# validation-board-final.net
KiCad netlist of a schematic drawn in EAGLE
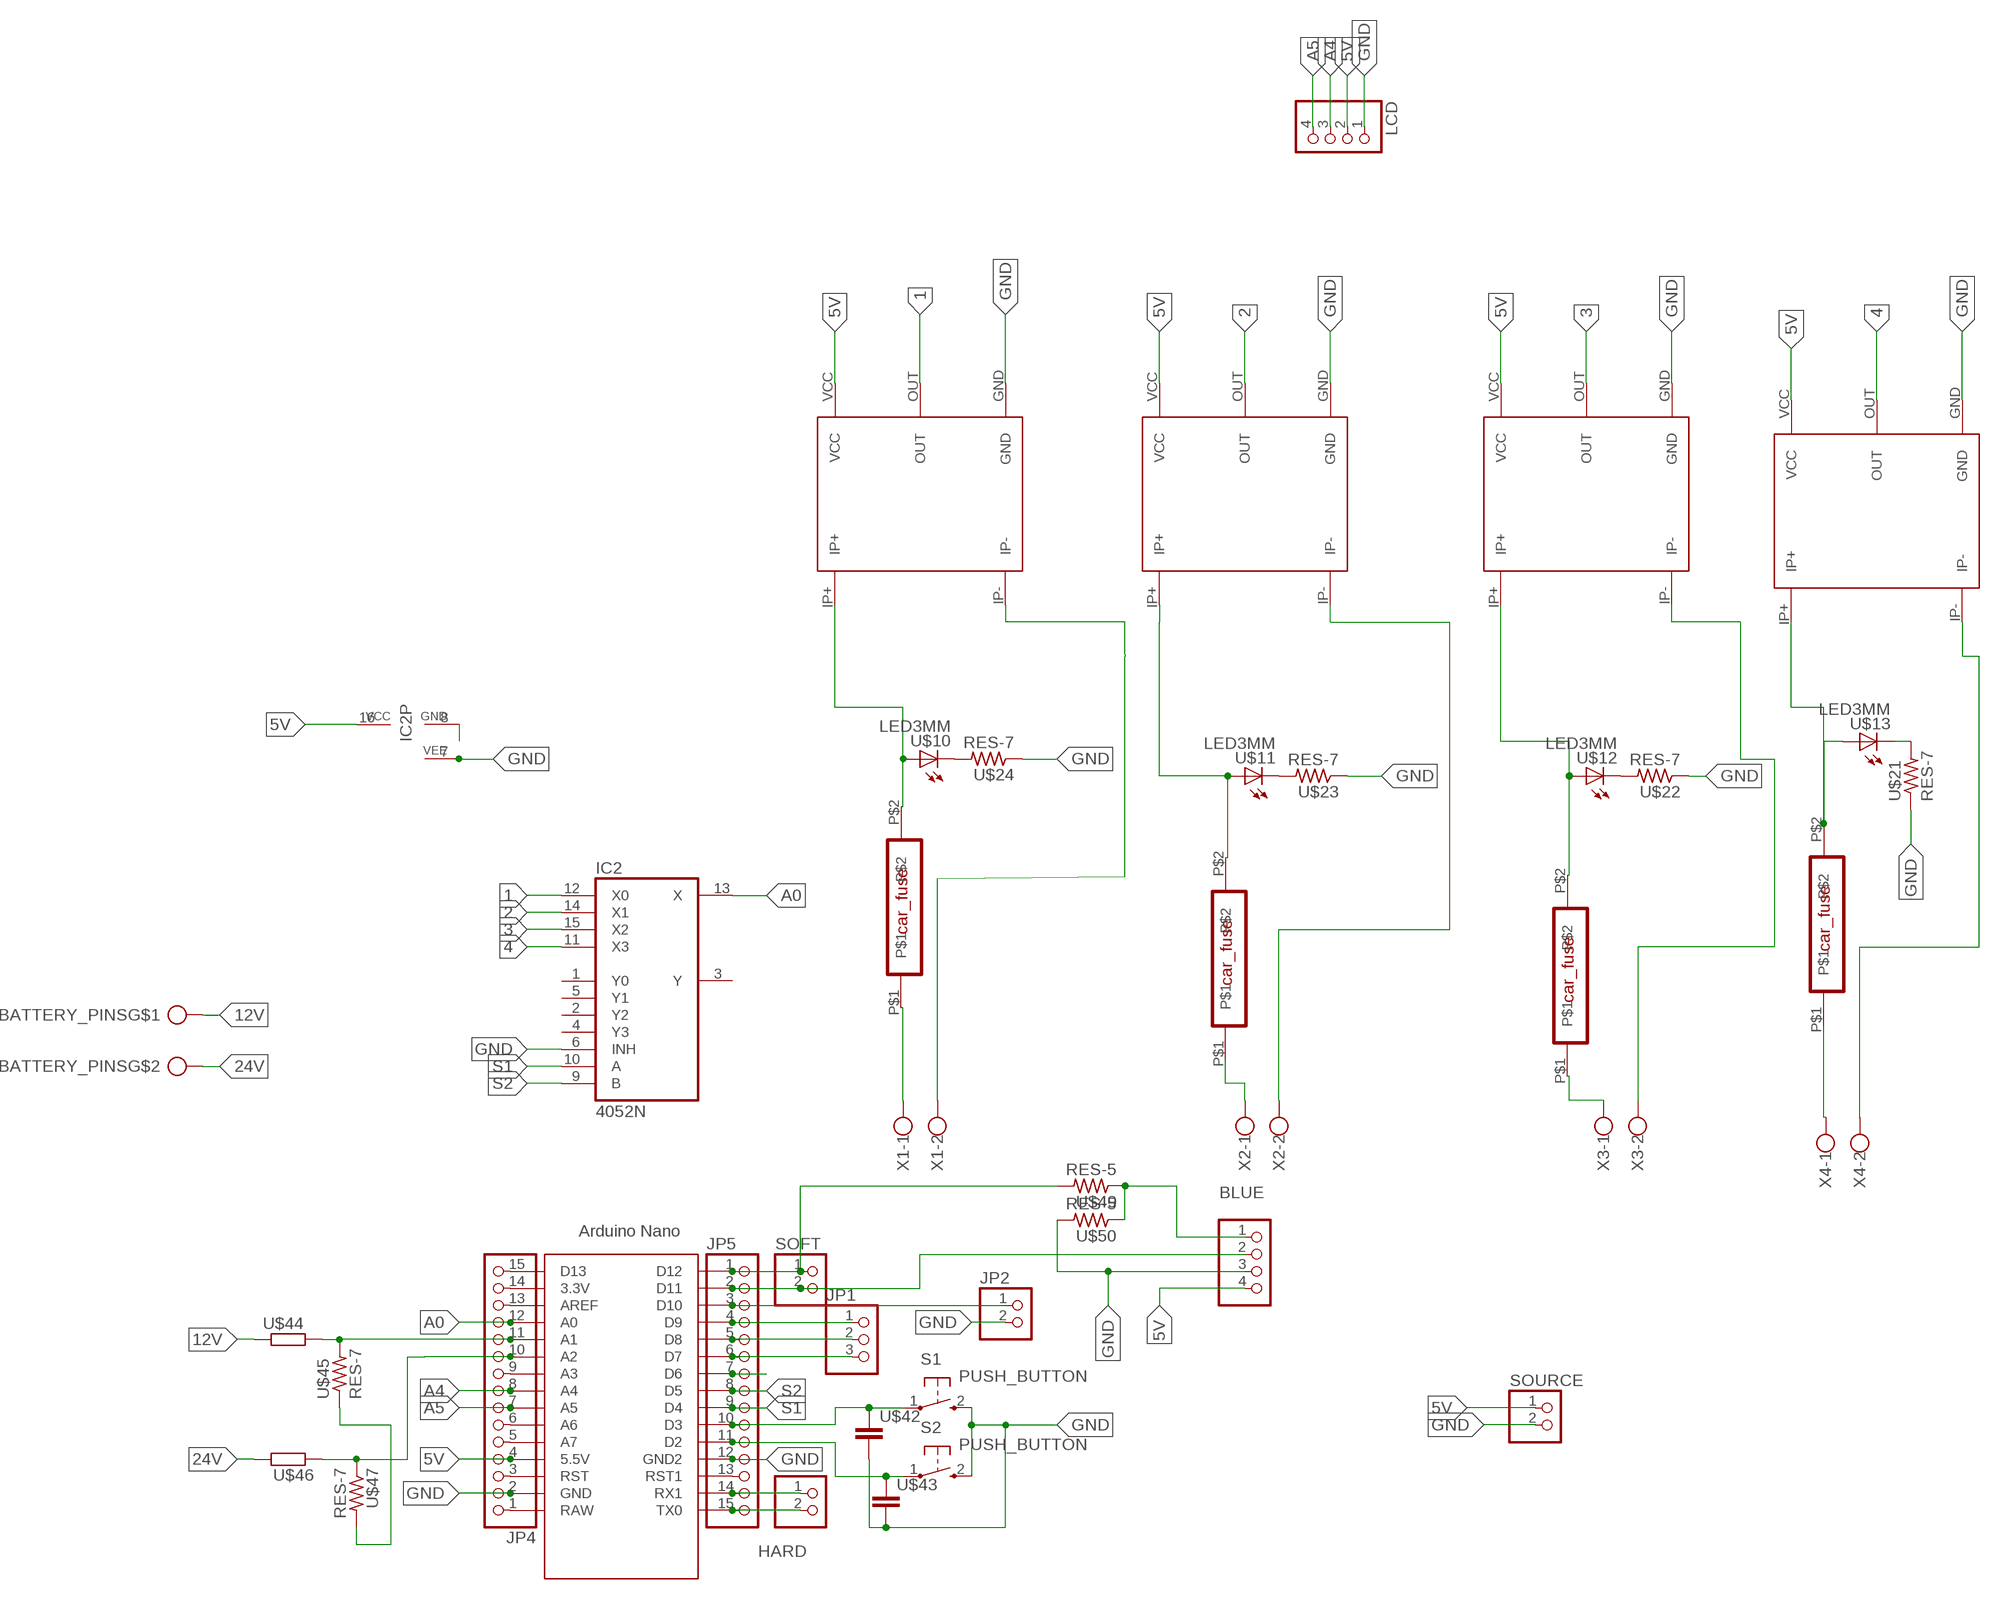
[diagram p0: schematic, sheet 1]

(export (version "E")
  (design (tool "Eeschema 10.0.6"))
  (components
    (comp (ref "BATTERY_PINS")
      (value "CON_PTR_2")
      (footprint "eagle-import:AK300_2")
      (libsource (lib "eagle-import") (part "CON_PTR_2"))
    )
    (comp (ref "BLUE")
      (value "PINHD-4_DATA")
      (footprint "eagle-import:1X04_DATA")
      (libsource (lib "eagle-import") (part "PINHD-4_DATA"))
    )
    (comp (ref "HARD")
      (value "PINHD-2_DATA")
      (footprint "eagle-import:1X02_DATA")
      (libsource (lib "eagle-import") (part "PINHD-2_DATA"))
    )
    (comp (ref "IC2")
      (value "4052N")
      (footprint "eagle-import:DIL16")
      (libsource (lib "eagle-import") (part "4052N"))
    )
    (comp (ref "JP1")
      (value "PINHD-3_DATA")
      (footprint "eagle-import:1X03_DATA")
      (libsource (lib "eagle-import") (part "PINHD-3_DATA"))
    )
    (comp (ref "JP2")
      (value "PINHD-2_DATA")
      (footprint "eagle-import:1X02_DATA")
      (libsource (lib "eagle-import") (part "PINHD-2_DATA"))
    )
    (comp (ref "JP4")
      (value "PINHD-1X15")
      (footprint "eagle-import:1X15")
      (libsource (lib "eagle-import") (part "PINHD-1X15"))
    )
    (comp (ref "JP5")
      (value "PINHD-1X15")
      (footprint "eagle-import:1X15")
      (libsource (lib "eagle-import") (part "PINHD-1X15"))
    )
    (comp (ref "LCD")
      (value "PINHD-4_DATA")
      (footprint "eagle-import:1X04_DATA")
      (libsource (lib "eagle-import") (part "PINHD-4_DATA"))
    )
    (comp (ref "S1")
      (value "PUSH_BUTTON")
      (footprint "eagle-import:B3F-10XX")
      (libsource (lib "eagle-import") (part "PUSH_BUTTON"))
    )
    (comp (ref "S2")
      (value "PUSH_BUTTON")
      (footprint "eagle-import:B3F-10XX")
      (libsource (lib "eagle-import") (part "PUSH_BUTTON"))
    )
    (comp (ref "SOFT")
      (value "PINHD-2_DATA")
      (footprint "eagle-import:1X02_DATA")
      (libsource (lib "eagle-import") (part "PINHD-2_DATA"))
    )
    (comp (ref "SOURCE")
      (value "PINHD-2_DATA")
      (footprint "eagle-import:1X02_DATA")
      (libsource (lib "eagle-import") (part "PINHD-2_DATA"))
    )
    (comp (ref "U$1")
      (value "ARDUINO_NANO")
      (footprint "eagle-import:NANO")
      (libsource (lib "eagle-import") (part "ARDUINO_NANO"))
    )
    (comp (ref "U$2")
      (value "CAR_FUSE")
      (footprint "eagle-import:CAR_FUSE")
      (libsource (lib "eagle-import") (part "CAR_FUSE"))
    )
    (comp (ref "U$3")
      (value "CAR_FUSE")
      (footprint "eagle-import:CAR_FUSE")
      (libsource (lib "eagle-import") (part "CAR_FUSE"))
    )
    (comp (ref "U$4")
      (value "CAR_FUSE")
      (footprint "eagle-import:CAR_FUSE")
      (libsource (lib "eagle-import") (part "CAR_FUSE"))
    )
    (comp (ref "U$5")
      (value "CAR_FUSE")
      (footprint "eagle-import:CAR_FUSE")
      (libsource (lib "eagle-import") (part "CAR_FUSE"))
    )
    (comp (ref "U$10")
      (value "LED3MM")
      (footprint "eagle-import:LED3MM")
      (libsource (lib "eagle-import") (part "LED3MM"))
    )
    (comp (ref "U$11")
      (value "LED3MM")
      (footprint "eagle-import:LED3MM")
      (libsource (lib "eagle-import") (part "LED3MM"))
    )
    (comp (ref "U$12")
      (value "LED3MM")
      (footprint "eagle-import:LED3MM")
      (libsource (lib "eagle-import") (part "LED3MM"))
    )
    (comp (ref "U$13")
      (value "LED3MM")
      (footprint "eagle-import:LED3MM")
      (libsource (lib "eagle-import") (part "LED3MM"))
    )
    (comp (ref "U$21")
      (value "RES-7")
      (footprint "eagle-import:0204_7")
      (libsource (lib "eagle-import") (part "RES-7"))
    )
    (comp (ref "U$22")
      (value "RES-7")
      (footprint "eagle-import:0204_7")
      (libsource (lib "eagle-import") (part "RES-7"))
    )
    (comp (ref "U$23")
      (value "RES-7")
      (footprint "eagle-import:0204_7")
      (libsource (lib "eagle-import") (part "RES-7"))
    )
    (comp (ref "U$24")
      (value "RES-7")
      (footprint "eagle-import:0204_7")
      (libsource (lib "eagle-import") (part "RES-7"))
    )
    (comp (ref "U$26")
      (value "ASC712_MODULE")
      (footprint "eagle-import:ASC712_MODULE")
      (libsource (lib "eagle-import") (part "ASC712_MODULE"))
    )
    (comp (ref "U$27")
      (value "ASC712_MODULE")
      (footprint "eagle-import:ASC712_MODULE")
      (libsource (lib "eagle-import") (part "ASC712_MODULE"))
    )
    (comp (ref "U$28")
      (value "ASC712_MODULE")
      (footprint "eagle-import:ASC712_MODULE")
      (libsource (lib "eagle-import") (part "ASC712_MODULE"))
    )
    (comp (ref "U$29")
      (value "ASC712_MODULE")
      (footprint "eagle-import:ASC712_MODULE")
      (libsource (lib "eagle-import") (part "ASC712_MODULE"))
    )
    (comp (ref "U$42")
      (value "CAPACITOR")
      (footprint "eagle-import:C025-025X050")
      (libsource (lib "eagle-import") (part "CAPACITOR"))
    )
    (comp (ref "U$43")
      (value "CAPACITOR")
      (footprint "eagle-import:C025-025X050")
      (libsource (lib "eagle-import") (part "CAPACITOR"))
    )
    (comp (ref "U$44")
      (value "R-EU_0207/10")
      (footprint "eagle-import:0207_10")
      (libsource (lib "eagle-import") (part "R-EU_0207/10"))
    )
    (comp (ref "U$45")
      (value "RES-7")
      (footprint "eagle-import:0204_7")
      (libsource (lib "eagle-import") (part "RES-7"))
    )
    (comp (ref "U$46")
      (value "R-EU_0207/10")
      (footprint "eagle-import:0207_10")
      (libsource (lib "eagle-import") (part "R-EU_0207/10"))
    )
    (comp (ref "U$47")
      (value "RES-7")
      (footprint "eagle-import:0204_7")
      (libsource (lib "eagle-import") (part "RES-7"))
    )
    (comp (ref "U$49")
      (value "RES-5")
      (footprint "eagle-import:0204_5")
      (libsource (lib "eagle-import") (part "RES-5"))
    )
    (comp (ref "U$50")
      (value "RES-5")
      (footprint "eagle-import:0204_5")
      (libsource (lib "eagle-import") (part "RES-5"))
    )
    (comp (ref "X1")
      (value "ROSTA.POWER")
      (footprint "eagle-import:W239-302")
      (libsource (lib "eagle-import") (part "ROSTA.POWER"))
    )
    (comp (ref "X2")
      (value "ROSTA.POWER")
      (footprint "eagle-import:W239-302")
      (libsource (lib "eagle-import") (part "ROSTA.POWER"))
    )
    (comp (ref "X3")
      (value "ROSTA.POWER")
      (footprint "eagle-import:W239-302")
      (libsource (lib "eagle-import") (part "ROSTA.POWER"))
    )
    (comp (ref "X4")
      (value "ROSTA.POWER")
      (footprint "eagle-import:W239-302")
      (libsource (lib "eagle-import") (part "ROSTA.POWER"))
    )
  )
  (nets
    (net (code "1") (name "1") (class "Default")
      (node (ref "IC2") (pin "12") (pinfunction "X0_12") (pintype "bidirectional"))
      (node (ref "U$26") (pin "OUT") (pinfunction "OUT_OUT") (pintype "bidirectional"))
    )
    (net (code "2") (name "2") (class "Default")
      (node (ref "IC2") (pin "14") (pinfunction "X1_14") (pintype "bidirectional"))
      (node (ref "U$27") (pin "OUT") (pinfunction "OUT_OUT") (pintype "bidirectional"))
    )
    (net (code "3") (name "3") (class "Default")
      (node (ref "IC2") (pin "15") (pinfunction "X2_15") (pintype "bidirectional"))
      (node (ref "U$28") (pin "OUT") (pinfunction "OUT_OUT") (pintype "bidirectional"))
    )
    (net (code "4") (name "4") (class "Default")
      (node (ref "IC2") (pin "11") (pinfunction "X3_11") (pintype "bidirectional"))
      (node (ref "U$29") (pin "OUT") (pinfunction "OUT_OUT") (pintype "bidirectional"))
    )
    (net (code "5") (name "5V") (class "Default")
      (node (ref "BLUE") (pin "4") (pinfunction "4_4") (pintype "passive"))
      (node (ref "IC2") (pin "16") (pinfunction "VCC_16") (pintype "power_in"))
      (node (ref "JP4") (pin "4") (pinfunction "4_4") (pintype "passive"))
      (node (ref "LCD") (pin "2") (pinfunction "2_2") (pintype "passive"))
      (node (ref "SOURCE") (pin "1") (pinfunction "1_1") (pintype "passive"))
      (node (ref "U$1") (pin "5V") (pinfunction "5.5V_5V") (pintype "bidirectional"))
      (node (ref "U$26") (pin "VCC") (pinfunction "VCC_VCC") (pintype "bidirectional"))
      (node (ref "U$27") (pin "VCC") (pinfunction "VCC_VCC") (pintype "bidirectional"))
      (node (ref "U$28") (pin "VCC") (pinfunction "VCC_VCC") (pintype "bidirectional"))
      (node (ref "U$29") (pin "VCC") (pinfunction "VCC_VCC") (pintype "bidirectional"))
    )
    (net (code "6") (name "12V") (class "Default")
      (node (ref "BATTERY_PINS") (pin "1") (pinfunction "KL_1") (pintype "passive"))
      (node (ref "U$44") (pin "1") (pinfunction "1_1") (pintype "passive"))
    )
    (net (code "7") (name "24V") (class "Default")
      (node (ref "BATTERY_PINS") (pin "2") (pinfunction "KL_2") (pintype "passive"))
      (node (ref "U$46") (pin "2") (pinfunction "2_2") (pintype "passive"))
    )
    (net (code "8") (name "A0") (class "Default")
      (node (ref "IC2") (pin "13") (pinfunction "X_13") (pintype "bidirectional"))
      (node (ref "JP4") (pin "12") (pinfunction "12_12") (pintype "passive"))
      (node (ref "U$1") (pin "A0") (pinfunction "A0_A0") (pintype "bidirectional"))
    )
    (net (code "9") (name "A4") (class "Default")
      (node (ref "JP4") (pin "8") (pinfunction "8_8") (pintype "passive"))
      (node (ref "LCD") (pin "3") (pinfunction "3_3") (pintype "passive"))
      (node (ref "U$1") (pin "A4") (pinfunction "A4_A4") (pintype "bidirectional"))
    )
    (net (code "10") (name "A5") (class "Default")
      (node (ref "JP4") (pin "7") (pinfunction "7_7") (pintype "passive"))
      (node (ref "LCD") (pin "4") (pinfunction "4_4") (pintype "passive"))
      (node (ref "U$1") (pin "A5") (pinfunction "A5_A5") (pintype "bidirectional"))
    )
    (net (code "11") (name "GND") (class "Default")
      (node (ref "BLUE") (pin "3") (pinfunction "3_3") (pintype "passive"))
      (node (ref "IC2") (pin "6") (pinfunction "INH_6") (pintype "input"))
      (node (ref "IC2") (pin "7") (pinfunction "VEE_7") (pintype "power_in"))
      (node (ref "JP2") (pin "2") (pinfunction "2_2") (pintype "passive"))
      (node (ref "JP4") (pin "2") (pinfunction "2_2") (pintype "passive"))
      (node (ref "JP5") (pin "12") (pinfunction "12_12") (pintype "passive"))
      (node (ref "LCD") (pin "1") (pinfunction "1_1") (pintype "passive"))
      (node (ref "S1") (pin "2") (pinfunction "S_2") (pintype "passive"))
      (node (ref "S2") (pin "2") (pinfunction "S_2") (pintype "passive"))
      (node (ref "SOURCE") (pin "2") (pinfunction "2_2") (pintype "passive"))
      (node (ref "U$1") (pin "GND") (pinfunction "GND_GND") (pintype "bidirectional"))
      (node (ref "U$1") (pin "GND1") (pinfunction "GND2_GND1") (pintype "bidirectional"))
      (node (ref "U$21") (pin "1") (pinfunction "1_1") (pintype "passive"))
      (node (ref "U$22") (pin "1") (pinfunction "1_1") (pintype "passive"))
      (node (ref "U$23") (pin "1") (pinfunction "1_1") (pintype "passive"))
      (node (ref "U$24") (pin "1") (pinfunction "1_1") (pintype "passive"))
      (node (ref "U$26") (pin "GND") (pinfunction "GND_GND") (pintype "bidirectional"))
      (node (ref "U$27") (pin "GND") (pinfunction "GND_GND") (pintype "bidirectional"))
      (node (ref "U$28") (pin "GND") (pinfunction "GND_GND") (pintype "bidirectional"))
      (node (ref "U$29") (pin "GND") (pinfunction "GND_GND") (pintype "bidirectional"))
      (node (ref "U$42") (pin "2") (pinfunction "2_2") (pintype "passive"))
      (node (ref "U$43") (pin "2") (pinfunction "2_2") (pintype "passive"))
      (node (ref "U$50") (pin "2") (pinfunction "2_2") (pintype "passive"))
    )
    (net (code "12") (name "Net-(BLUE-Pad1)") (class "Default")
      (node (ref "BLUE") (pin "1") (pinfunction "1_1") (pintype "passive"))
      (node (ref "U$49") (pin "1") (pinfunction "1_1") (pintype "passive"))
      (node (ref "U$50") (pin "1") (pinfunction "1_1") (pintype "passive"))
    )
    (net (code "13") (name "Net-(BLUE-Pad2)") (class "Default")
      (node (ref "BLUE") (pin "2") (pinfunction "2_2") (pintype "passive"))
      (node (ref "JP5") (pin "2") (pinfunction "2_2") (pintype "passive"))
      (node (ref "SOFT") (pin "2") (pinfunction "2_2") (pintype "passive"))
      (node (ref "U$1") (pin "D11") (pinfunction "D11_D11") (pintype "bidirectional"))
    )
    (net (code "14") (name "Net-(HARD-Pad1)") (class "Default")
      (node (ref "HARD") (pin "1") (pinfunction "1_1") (pintype "passive"))
      (node (ref "JP5") (pin "14") (pinfunction "14_14") (pintype "passive"))
      (node (ref "U$1") (pin "RX1") (pinfunction "RX1_RX1") (pintype "bidirectional"))
    )
    (net (code "15") (name "Net-(HARD-Pad2)") (class "Default")
      (node (ref "HARD") (pin "2") (pinfunction "2_2") (pintype "passive"))
      (node (ref "JP5") (pin "15") (pinfunction "15_15") (pintype "passive"))
      (node (ref "U$1") (pin "TX0") (pinfunction "TX0_TX0") (pintype "bidirectional"))
    )
    (net (code "16") (name "Net-(JP1-Pad1)") (class "Default")
      (node (ref "JP1") (pin "1") (pinfunction "1_1") (pintype "passive"))
      (node (ref "JP5") (pin "4") (pinfunction "4_4") (pintype "passive"))
      (node (ref "U$1") (pin "D9") (pinfunction "D9_D9") (pintype "bidirectional"))
    )
    (net (code "17") (name "Net-(JP1-Pad2)") (class "Default")
      (node (ref "JP1") (pin "2") (pinfunction "2_2") (pintype "passive"))
      (node (ref "JP5") (pin "5") (pinfunction "5_5") (pintype "passive"))
      (node (ref "U$1") (pin "D8") (pinfunction "D8_D8") (pintype "bidirectional"))
    )
    (net (code "18") (name "Net-(JP1-Pad3)") (class "Default")
      (node (ref "JP1") (pin "3") (pinfunction "3_3") (pintype "passive"))
      (node (ref "JP5") (pin "6") (pinfunction "6_6") (pintype "passive"))
      (node (ref "U$1") (pin "D7") (pinfunction "D7_D7") (pintype "bidirectional"))
    )
    (net (code "19") (name "Net-(JP2-Pad1)") (class "Default")
      (node (ref "JP2") (pin "1") (pinfunction "1_1") (pintype "passive"))
      (node (ref "JP5") (pin "3") (pinfunction "3_3") (pintype "passive"))
      (node (ref "U$1") (pin "D10") (pinfunction "D10_D10") (pintype "bidirectional"))
    )
    (net (code "20") (name "Net-(JP4-Pad1)") (class "Default")
      (node (ref "JP4") (pin "1") (pinfunction "1_1") (pintype "passive"))
      (node (ref "U$1") (pin "RAW") (pinfunction "RAW_RAW") (pintype "bidirectional"))
    )
    (net (code "21") (name "Net-(JP4-Pad3)") (class "Default")
      (node (ref "JP4") (pin "3") (pinfunction "3_3") (pintype "passive"))
      (node (ref "U$1") (pin "RST") (pinfunction "RST_RST") (pintype "bidirectional"))
    )
    (net (code "22") (name "Net-(JP4-Pad5)") (class "Default")
      (node (ref "JP4") (pin "5") (pinfunction "5_5") (pintype "passive"))
      (node (ref "U$1") (pin "A7") (pinfunction "A7_A7") (pintype "bidirectional"))
    )
    (net (code "23") (name "Net-(JP4-Pad6)") (class "Default")
      (node (ref "JP4") (pin "6") (pinfunction "6_6") (pintype "passive"))
      (node (ref "U$1") (pin "A6") (pinfunction "A6_A6") (pintype "bidirectional"))
    )
    (net (code "24") (name "Net-(JP4-Pad9)") (class "Default")
      (node (ref "JP4") (pin "9") (pinfunction "9_9") (pintype "passive"))
      (node (ref "U$1") (pin "A3") (pinfunction "A3_A3") (pintype "bidirectional"))
    )
    (net (code "25") (name "Net-(JP4-Pad10)") (class "Default")
      (node (ref "JP4") (pin "10") (pinfunction "10_10") (pintype "passive"))
      (node (ref "U$1") (pin "A2") (pinfunction "A2_A2") (pintype "bidirectional"))
      (node (ref "U$46") (pin "1") (pinfunction "1_1") (pintype "passive"))
      (node (ref "U$47") (pin "1") (pinfunction "1_1") (pintype "passive"))
    )
    (net (code "26") (name "Net-(JP4-Pad11)") (class "Default")
      (node (ref "JP4") (pin "11") (pinfunction "11_11") (pintype "passive"))
      (node (ref "U$1") (pin "A1") (pinfunction "A1_A1") (pintype "bidirectional"))
      (node (ref "U$44") (pin "2") (pinfunction "2_2") (pintype "passive"))
      (node (ref "U$45") (pin "2") (pinfunction "2_2") (pintype "passive"))
    )
    (net (code "27") (name "Net-(JP4-Pad13)") (class "Default")
      (node (ref "JP4") (pin "13") (pinfunction "13_13") (pintype "passive"))
      (node (ref "U$1") (pin "AREF") (pinfunction "AREF_AREF") (pintype "bidirectional"))
    )
    (net (code "28") (name "Net-(JP4-Pad14)") (class "Default")
      (node (ref "JP4") (pin "14") (pinfunction "14_14") (pintype "passive"))
      (node (ref "U$1") (pin "3.3V") (pinfunction "3.3V_3.3V") (pintype "bidirectional"))
    )
    (net (code "29") (name "Net-(JP4-Pad15)") (class "Default")
      (node (ref "JP4") (pin "15") (pinfunction "15_15") (pintype "passive"))
      (node (ref "U$1") (pin "D13") (pinfunction "D13_D13") (pintype "bidirectional"))
    )
    (net (code "30") (name "Net-(JP5-Pad1)") (class "Default")
      (node (ref "JP5") (pin "1") (pinfunction "1_1") (pintype "passive"))
      (node (ref "SOFT") (pin "1") (pinfunction "1_1") (pintype "passive"))
      (node (ref "U$1") (pin "D12") (pinfunction "D12_D12") (pintype "bidirectional"))
      (node (ref "U$49") (pin "2") (pinfunction "2_2") (pintype "passive"))
    )
    (net (code "31") (name "Net-(JP5-Pad7)") (class "Default")
      (node (ref "JP5") (pin "7") (pinfunction "7_7") (pintype "passive"))
      (node (ref "U$1") (pin "D6") (pinfunction "D6_D6") (pintype "bidirectional"))
    )
    (net (code "32") (name "Net-(JP5-Pad13)") (class "Default")
      (node (ref "JP5") (pin "13") (pinfunction "13_13") (pintype "passive"))
      (node (ref "U$1") (pin "RST1") (pinfunction "RST1_RST1") (pintype "bidirectional"))
    )
    (net (code "33") (name "Net-(S1-P)") (class "Default")
      (node (ref "JP5") (pin "10") (pinfunction "10_10") (pintype "passive"))
      (node (ref "S1") (pin "1") (pinfunction "P_1") (pintype "passive"))
      (node (ref "U$1") (pin "D3") (pinfunction "D3_D3") (pintype "bidirectional"))
      (node (ref "U$42") (pin "1") (pinfunction "1_1") (pintype "passive"))
    )
    (net (code "34") (name "Net-(S2-P)") (class "Default")
      (node (ref "JP5") (pin "11") (pinfunction "11_11") (pintype "passive"))
      (node (ref "S2") (pin "1") (pinfunction "P_1") (pintype "passive"))
      (node (ref "U$1") (pin "D2") (pinfunction "D2_D2") (pintype "bidirectional"))
      (node (ref "U$43") (pin "1") (pinfunction "1_1") (pintype "passive"))
    )
    (net (code "35") (name "Net-(U$10-C)") (class "Default")
      (node (ref "U$10") (pin "K") (pinfunction "C_K") (pintype "passive"))
      (node (ref "U$24") (pin "2") (pinfunction "2_2") (pintype "passive"))
    )
    (net (code "36") (name "Net-(U$10-PadA)") (class "Default")
      (node (ref "U$10") (pin "A") (pinfunction "A_A") (pintype "passive"))
      (node (ref "U$2") (pin "P$2") (pinfunction "P$2_P$2") (pintype "bidirectional"))
      (node (ref "U$26") (pin "IP+") (pinfunction "IP+_IP+") (pintype "bidirectional"))
    )
    (net (code "37") (name "Net-(U$11-C)") (class "Default")
      (node (ref "U$11") (pin "K") (pinfunction "C_K") (pintype "passive"))
      (node (ref "U$23") (pin "2") (pinfunction "2_2") (pintype "passive"))
    )
    (net (code "38") (name "Net-(U$11-PadA)") (class "Default")
      (node (ref "U$11") (pin "A") (pinfunction "A_A") (pintype "passive"))
      (node (ref "U$27") (pin "IP+") (pinfunction "IP+_IP+") (pintype "bidirectional"))
      (node (ref "U$3") (pin "P$2") (pinfunction "P$2_P$2") (pintype "bidirectional"))
    )
    (net (code "39") (name "Net-(U$12-C)") (class "Default")
      (node (ref "U$12") (pin "K") (pinfunction "C_K") (pintype "passive"))
      (node (ref "U$22") (pin "2") (pinfunction "2_2") (pintype "passive"))
    )
    (net (code "40") (name "Net-(U$12-PadA)") (class "Default")
      (node (ref "U$12") (pin "A") (pinfunction "A_A") (pintype "passive"))
      (node (ref "U$28") (pin "IP+") (pinfunction "IP+_IP+") (pintype "bidirectional"))
      (node (ref "U$4") (pin "P$2") (pinfunction "P$2_P$2") (pintype "bidirectional"))
    )
    (net (code "41") (name "Net-(U$13-C)") (class "Default")
      (node (ref "U$13") (pin "K") (pinfunction "C_K") (pintype "passive"))
      (node (ref "U$21") (pin "2") (pinfunction "2_2") (pintype "passive"))
    )
    (net (code "42") (name "Net-(U$13-PadA)") (class "Default")
      (node (ref "U$13") (pin "A") (pinfunction "A_A") (pintype "passive"))
      (node (ref "U$29") (pin "IP+") (pinfunction "IP+_IP+") (pintype "bidirectional"))
      (node (ref "U$5") (pin "P$2") (pinfunction "P$2_P$2") (pintype "bidirectional"))
    )
    (net (code "43") (name "Net-(U$45-Pad1)") (class "Default")
      (node (ref "U$45") (pin "1") (pinfunction "1_1") (pintype "passive"))
      (node (ref "U$47") (pin "2") (pinfunction "2_2") (pintype "passive"))
    )
    (net (code "44") (name "Net-(X1A-KL)") (class "Default")
      (node (ref "U$2") (pin "P$1") (pinfunction "P$1_P$1") (pintype "bidirectional"))
      (node (ref "X1") (pin "1") (pinfunction "KL_1") (pintype "passive"))
    )
    (net (code "45") (name "Net-(X1B-KL)") (class "Default")
      (node (ref "U$26") (pin "IP-") (pinfunction "IP-_IP-") (pintype "bidirectional"))
      (node (ref "X1") (pin "2") (pinfunction "KL_2") (pintype "passive"))
    )
    (net (code "46") (name "Net-(X2A-KL)") (class "Default")
      (node (ref "U$3") (pin "P$1") (pinfunction "P$1_P$1") (pintype "bidirectional"))
      (node (ref "X2") (pin "1") (pinfunction "KL_1") (pintype "passive"))
    )
    (net (code "47") (name "Net-(X2B-KL)") (class "Default")
      (node (ref "U$27") (pin "IP-") (pinfunction "IP-_IP-") (pintype "bidirectional"))
      (node (ref "X2") (pin "2") (pinfunction "KL_2") (pintype "passive"))
    )
    (net (code "48") (name "Net-(X3A-KL)") (class "Default")
      (node (ref "U$4") (pin "P$1") (pinfunction "P$1_P$1") (pintype "bidirectional"))
      (node (ref "X3") (pin "1") (pinfunction "KL_1") (pintype "passive"))
    )
    (net (code "49") (name "Net-(X3B-KL)") (class "Default")
      (node (ref "U$28") (pin "IP-") (pinfunction "IP-_IP-") (pintype "bidirectional"))
      (node (ref "X3") (pin "2") (pinfunction "KL_2") (pintype "passive"))
    )
    (net (code "50") (name "Net-(X4A-KL)") (class "Default")
      (node (ref "U$5") (pin "P$1") (pinfunction "P$1_P$1") (pintype "bidirectional"))
      (node (ref "X4") (pin "1") (pinfunction "KL_1") (pintype "passive"))
    )
    (net (code "51") (name "Net-(X4B-KL)") (class "Default")
      (node (ref "U$29") (pin "IP-") (pinfunction "IP-_IP-") (pintype "bidirectional"))
      (node (ref "X4") (pin "2") (pinfunction "KL_2") (pintype "passive"))
    )
    (net (code "52") (name "S1") (class "Default")
      (node (ref "IC2") (pin "10") (pinfunction "A_10") (pintype "input"))
      (node (ref "JP5") (pin "9") (pinfunction "9_9") (pintype "passive"))
      (node (ref "U$1") (pin "D4") (pinfunction "D4_D4") (pintype "bidirectional"))
    )
    (net (code "53") (name "S2") (class "Default")
      (node (ref "IC2") (pin "9") (pinfunction "B_9") (pintype "input"))
      (node (ref "JP5") (pin "8") (pinfunction "8_8") (pintype "passive"))
      (node (ref "U$1") (pin "D5") (pinfunction "D5_D5") (pintype "bidirectional"))
    )
    (net (code "54") (name "unconnected-(IC2A-Y-Pad3)") (class "Default")
      (node (ref "IC2") (pin "3") (pinfunction "Y_3") (pintype "bidirectional"))
    )
    (net (code "55") (name "unconnected-(IC2A-Y0-Pad1)") (class "Default")
      (node (ref "IC2") (pin "1") (pinfunction "Y0_1") (pintype "bidirectional"))
    )
    (net (code "56") (name "unconnected-(IC2A-Y1-Pad5)") (class "Default")
      (node (ref "IC2") (pin "5") (pinfunction "Y1_5") (pintype "bidirectional"))
    )
    (net (code "57") (name "unconnected-(IC2A-Y2-Pad2)") (class "Default")
      (node (ref "IC2") (pin "2") (pinfunction "Y2_2") (pintype "bidirectional"))
    )
    (net (code "58") (name "unconnected-(IC2A-Y3-Pad4)") (class "Default")
      (node (ref "IC2") (pin "4") (pinfunction "Y3_4") (pintype "bidirectional"))
    )
    (net (code "59") (name "unconnected-(IC2B-GND-Pad8)") (class "Default")
      (node (ref "IC2") (pin "8") (pinfunction "GND_8") (pintype "power_in"))
    )
  )
)
